# sensor_v1.net
KiCad netlist of a schematic drawn in EAGLE
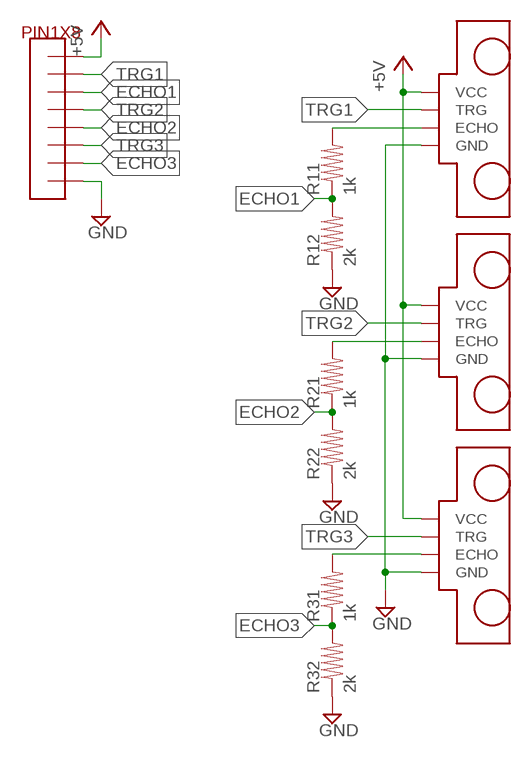
[diagram p0: schematic, sheet 1]

(export (version "E")
  (design (tool "Eeschema 10.0.6"))
  (components
    (comp (ref "R11")
      (value "1k")
      (footprint "eagle-import:SMD_REG0805")
      (libsource (lib "eagle-import") (part "SMD_REG0805"))
    )
    (comp (ref "R12")
      (value "2k")
      (footprint "eagle-import:SMD_REG0805")
      (libsource (lib "eagle-import") (part "SMD_REG0805"))
    )
    (comp (ref "R21")
      (value "1k")
      (footprint "eagle-import:SMD_REG0805")
      (libsource (lib "eagle-import") (part "SMD_REG0805"))
    )
    (comp (ref "R22")
      (value "2k")
      (footprint "eagle-import:SMD_REG0805")
      (libsource (lib "eagle-import") (part "SMD_REG0805"))
    )
    (comp (ref "R31")
      (value "1k")
      (footprint "eagle-import:SMD_REG0805")
      (libsource (lib "eagle-import") (part "SMD_REG0805"))
    )
    (comp (ref "R32")
      (value "2k")
      (footprint "eagle-import:SMD_REG0805")
      (libsource (lib "eagle-import") (part "SMD_REG0805"))
    )
    (comp (ref "U$1")
      (value "HCSR04")
      (footprint "eagle-import:HCSR04")
      (libsource (lib "eagle-import") (part "HCSR04"))
    )
    (comp (ref "U$2")
      (value "HCSR04")
      (footprint "eagle-import:HCSR04")
      (libsource (lib "eagle-import") (part "HCSR04"))
    )
    (comp (ref "U$3")
      (value "HCSR04")
      (footprint "eagle-import:HCSR04")
      (libsource (lib "eagle-import") (part "HCSR04"))
    )
    (comp (ref "U$4")
      (value "PIN1X8_254")
      (footprint "eagle-import:PIN1X8_254")
      (libsource (lib "eagle-import") (part "PIN1X8_254"))
    )
  )
  (nets
    (net (code "1") (name "+5V") (class "Default")
      (node (ref "U$1") (pin "VCC") (pinfunction "VCC_VCC") (pintype "bidirectional"))
      (node (ref "U$2") (pin "VCC") (pinfunction "VCC_VCC") (pintype "bidirectional"))
      (node (ref "U$3") (pin "VCC") (pinfunction "VCC_VCC") (pintype "bidirectional"))
      (node (ref "U$4") (pin "P$1") (pinfunction "P1_P$1") (pintype "bidirectional"))
    )
    (net (code "2") (name "ECHO1") (class "Default")
      (node (ref "R11") (pin "P1") (pinfunction "P1_P1") (pintype "bidirectional"))
      (node (ref "R12") (pin "P2") (pinfunction "P2_P2") (pintype "bidirectional"))
      (node (ref "U$4") (pin "P$3") (pinfunction "P3_P$3") (pintype "bidirectional"))
    )
    (net (code "3") (name "ECHO2") (class "Default")
      (node (ref "R21") (pin "P1") (pinfunction "P1_P1") (pintype "bidirectional"))
      (node (ref "R22") (pin "P2") (pinfunction "P2_P2") (pintype "bidirectional"))
      (node (ref "U$4") (pin "P$5") (pinfunction "P5_P$5") (pintype "bidirectional"))
    )
    (net (code "4") (name "ECHO3") (class "Default")
      (node (ref "R31") (pin "P1") (pinfunction "P1_P1") (pintype "bidirectional"))
      (node (ref "R32") (pin "P2") (pinfunction "P2_P2") (pintype "bidirectional"))
      (node (ref "U$4") (pin "P$7") (pinfunction "P7_P$7") (pintype "bidirectional"))
    )
    (net (code "5") (name "GND") (class "Default")
      (node (ref "R12") (pin "P1") (pinfunction "P1_P1") (pintype "bidirectional"))
      (node (ref "R22") (pin "P1") (pinfunction "P1_P1") (pintype "bidirectional"))
      (node (ref "R32") (pin "P1") (pinfunction "P1_P1") (pintype "bidirectional"))
      (node (ref "U$1") (pin "GND") (pinfunction "GND_GND") (pintype "bidirectional"))
      (node (ref "U$2") (pin "GND") (pinfunction "GND_GND") (pintype "bidirectional"))
      (node (ref "U$3") (pin "GND") (pinfunction "GND_GND") (pintype "bidirectional"))
      (node (ref "U$4") (pin "P$8") (pinfunction "P8_P$8") (pintype "bidirectional"))
    )
    (net (code "6") (name "Net-(R11-PadP2)") (class "Default")
      (node (ref "R11") (pin "P2") (pinfunction "P2_P2") (pintype "bidirectional"))
      (node (ref "U$1") (pin "ECHO") (pinfunction "ECHO_ECHO") (pintype "bidirectional"))
    )
    (net (code "7") (name "Net-(R21-PadP2)") (class "Default")
      (node (ref "R21") (pin "P2") (pinfunction "P2_P2") (pintype "bidirectional"))
      (node (ref "U$2") (pin "ECHO") (pinfunction "ECHO_ECHO") (pintype "bidirectional"))
    )
    (net (code "8") (name "Net-(R31-PadP2)") (class "Default")
      (node (ref "R31") (pin "P2") (pinfunction "P2_P2") (pintype "bidirectional"))
      (node (ref "U$3") (pin "ECHO") (pinfunction "ECHO_ECHO") (pintype "bidirectional"))
    )
    (net (code "9") (name "TRG1") (class "Default")
      (node (ref "U$1") (pin "TRG") (pinfunction "TRG_TRG") (pintype "bidirectional"))
      (node (ref "U$4") (pin "P$2") (pinfunction "P2_P$2") (pintype "bidirectional"))
    )
    (net (code "10") (name "TRG2") (class "Default")
      (node (ref "U$2") (pin "TRG") (pinfunction "TRG_TRG") (pintype "bidirectional"))
      (node (ref "U$4") (pin "P$4") (pinfunction "P4_P$4") (pintype "bidirectional"))
    )
    (net (code "11") (name "TRG3") (class "Default")
      (node (ref "U$3") (pin "TRG") (pinfunction "TRG_TRG") (pintype "bidirectional"))
      (node (ref "U$4") (pin "P$6") (pinfunction "P6_P$6") (pintype "bidirectional"))
    )
  )
)
